# shoe_board-1.net
KiCad netlist of a schematic drawn in EAGLE
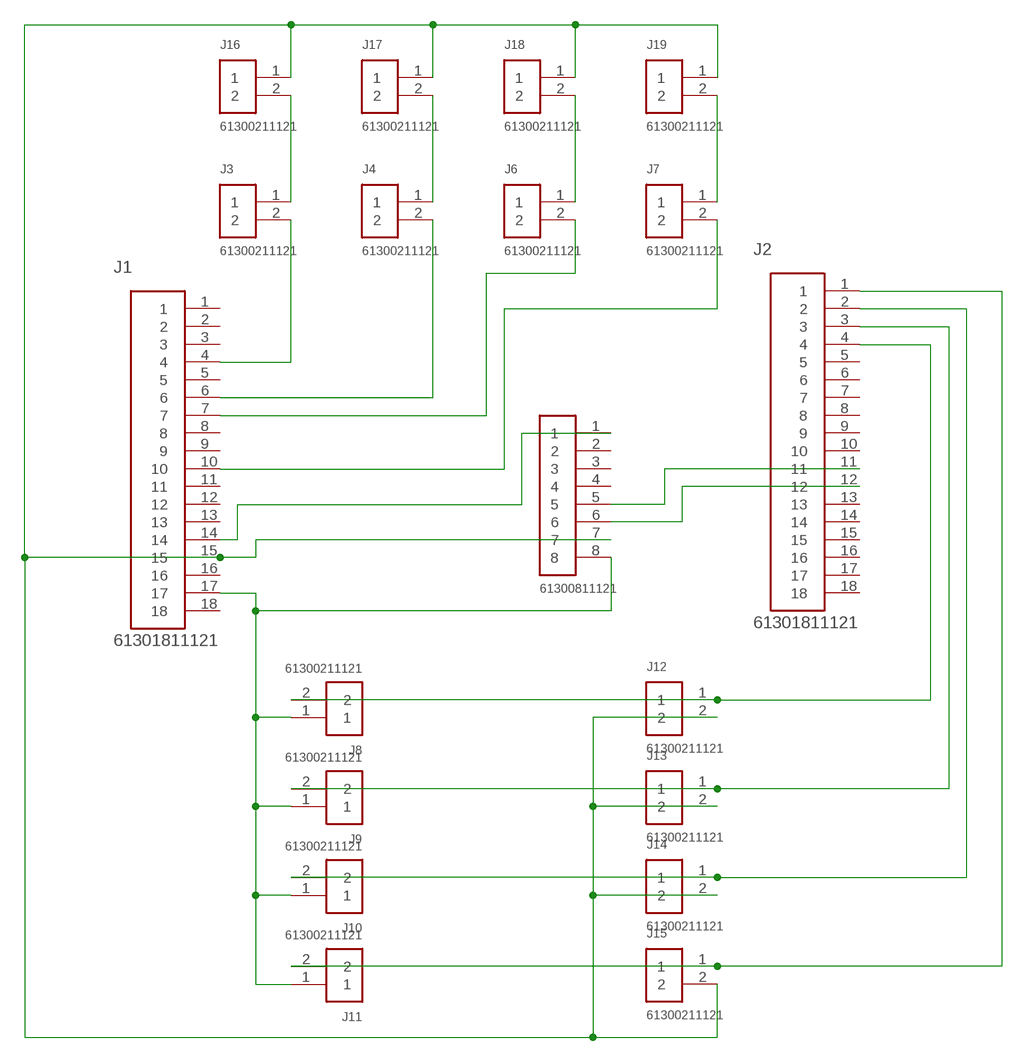
[diagram p0: schematic, sheet 1]

(export (version "E")
  (design (tool "Eeschema 10.0.6"))
  (components
    (comp (ref "J1")
      (value "61301811121")
      (footprint "eagle-import:61301811121")
      (fields
        (field (name "DIGIKEY_PART_NUMBER") "732-5328-ND")
        (field (name "MANUFACTURER") "Wurth Electronics Inc.")
        (field (name "CREATED_BY") "PCBLayout.com")
      )
      (libsource (lib "eagle-import") (part "61301811121"))
    )
    (comp (ref "J2")
      (value "61301811121")
      (footprint "eagle-import:61301811121")
      (fields
        (field (name "DIGIKEY_PART_NUMBER") "732-5328-ND")
        (field (name "MANUFACTURER") "Wurth Electronics Inc.")
        (field (name "CREATED_BY") "PCBLayout.com")
      )
      (libsource (lib "eagle-import") (part "61301811121"))
    )
    (comp (ref "J3")
      (value "61300211121")
      (footprint "eagle-import:61300211121")
      (fields
        (field (name "DIGI_KEY_PART_NUMBER") "732-5315-ND")
        (field (name "MANUFACTURER") "Wurth Electronics Inc.")
        (field (name "CREATED_BY") "PCBLayout.com")
      )
      (libsource (lib "eagle-import") (part "61300211121"))
    )
    (comp (ref "J4")
      (value "61300211121")
      (footprint "eagle-import:61300211121")
      (fields
        (field (name "DIGI_KEY_PART_NUMBER") "732-5315-ND")
        (field (name "MANUFACTURER") "Wurth Electronics Inc.")
        (field (name "CREATED_BY") "PCBLayout.com")
      )
      (libsource (lib "eagle-import") (part "61300211121"))
    )
    (comp (ref "J6")
      (value "61300211121")
      (footprint "eagle-import:61300211121")
      (fields
        (field (name "DIGI_KEY_PART_NUMBER") "732-5315-ND")
        (field (name "MANUFACTURER") "Wurth Electronics Inc.")
        (field (name "CREATED_BY") "PCBLayout.com")
      )
      (libsource (lib "eagle-import") (part "61300211121"))
    )
    (comp (ref "J7")
      (value "61300211121")
      (footprint "eagle-import:61300211121")
      (fields
        (field (name "DIGI_KEY_PART_NUMBER") "732-5315-ND")
        (field (name "MANUFACTURER") "Wurth Electronics Inc.")
        (field (name "CREATED_BY") "PCBLayout.com")
      )
      (libsource (lib "eagle-import") (part "61300211121"))
    )
    (comp (ref "J8")
      (value "61300211121")
      (footprint "eagle-import:61300211121")
      (fields
        (field (name "DIGI_KEY_PART_NUMBER") "732-5315-ND")
        (field (name "MANUFACTURER") "Wurth Electronics Inc.")
        (field (name "CREATED_BY") "PCBLayout.com")
      )
      (libsource (lib "eagle-import") (part "61300211121"))
    )
    (comp (ref "J9")
      (value "61300211121")
      (footprint "eagle-import:61300211121")
      (fields
        (field (name "DIGI_KEY_PART_NUMBER") "732-5315-ND")
        (field (name "MANUFACTURER") "Wurth Electronics Inc.")
        (field (name "CREATED_BY") "PCBLayout.com")
      )
      (libsource (lib "eagle-import") (part "61300211121"))
    )
    (comp (ref "J10")
      (value "61300211121")
      (footprint "eagle-import:61300211121")
      (fields
        (field (name "DIGI_KEY_PART_NUMBER") "732-5315-ND")
        (field (name "MANUFACTURER") "Wurth Electronics Inc.")
        (field (name "CREATED_BY") "PCBLayout.com")
      )
      (libsource (lib "eagle-import") (part "61300211121"))
    )
    (comp (ref "J11")
      (value "61300211121")
      (footprint "eagle-import:61300211121")
      (fields
        (field (name "DIGI_KEY_PART_NUMBER") "732-5315-ND")
        (field (name "MANUFACTURER") "Wurth Electronics Inc.")
        (field (name "CREATED_BY") "PCBLayout.com")
      )
      (libsource (lib "eagle-import") (part "61300211121"))
    )
    (comp (ref "J12")
      (value "61300211121")
      (footprint "eagle-import:61300211121")
      (fields
        (field (name "DIGI_KEY_PART_NUMBER") "732-5315-ND")
        (field (name "MANUFACTURER") "Wurth Electronics Inc.")
        (field (name "CREATED_BY") "PCBLayout.com")
      )
      (libsource (lib "eagle-import") (part "61300211121"))
    )
    (comp (ref "J13")
      (value "61300211121")
      (footprint "eagle-import:61300211121")
      (fields
        (field (name "DIGI_KEY_PART_NUMBER") "732-5315-ND")
        (field (name "MANUFACTURER") "Wurth Electronics Inc.")
        (field (name "CREATED_BY") "PCBLayout.com")
      )
      (libsource (lib "eagle-import") (part "61300211121"))
    )
    (comp (ref "J14")
      (value "61300211121")
      (footprint "eagle-import:61300211121")
      (fields
        (field (name "DIGI_KEY_PART_NUMBER") "732-5315-ND")
        (field (name "MANUFACTURER") "Wurth Electronics Inc.")
        (field (name "CREATED_BY") "PCBLayout.com")
      )
      (libsource (lib "eagle-import") (part "61300211121"))
    )
    (comp (ref "J15")
      (value "61300211121")
      (footprint "eagle-import:61300211121")
      (fields
        (field (name "DIGI_KEY_PART_NUMBER") "732-5315-ND")
        (field (name "MANUFACTURER") "Wurth Electronics Inc.")
        (field (name "CREATED_BY") "PCBLayout.com")
      )
      (libsource (lib "eagle-import") (part "61300211121"))
    )
    (comp (ref "J16")
      (value "61300211121")
      (footprint "eagle-import:61300211121")
      (fields
        (field (name "DIGI_KEY_PART_NUMBER") "732-5315-ND")
        (field (name "MANUFACTURER") "Wurth Electronics Inc.")
        (field (name "CREATED_BY") "PCBLayout.com")
      )
      (libsource (lib "eagle-import") (part "61300211121"))
    )
    (comp (ref "J17")
      (value "61300211121")
      (footprint "eagle-import:61300211121")
      (fields
        (field (name "DIGI_KEY_PART_NUMBER") "732-5315-ND")
        (field (name "MANUFACTURER") "Wurth Electronics Inc.")
        (field (name "CREATED_BY") "PCBLayout.com")
      )
      (libsource (lib "eagle-import") (part "61300211121"))
    )
    (comp (ref "J18")
      (value "61300211121")
      (footprint "eagle-import:61300211121")
      (fields
        (field (name "DIGI_KEY_PART_NUMBER") "732-5315-ND")
        (field (name "MANUFACTURER") "Wurth Electronics Inc.")
        (field (name "CREATED_BY") "PCBLayout.com")
      )
      (libsource (lib "eagle-import") (part "61300211121"))
    )
    (comp (ref "J19")
      (value "61300211121")
      (footprint "eagle-import:61300211121")
      (fields
        (field (name "DIGI_KEY_PART_NUMBER") "732-5315-ND")
        (field (name "MANUFACTURER") "Wurth Electronics Inc.")
        (field (name "CREATED_BY") "PCBLayout.com")
      )
      (libsource (lib "eagle-import") (part "61300211121"))
    )
    (comp (ref "J20")
      (value "61300811121")
      (footprint "eagle-import:61300811121")
      (fields
        (field (name "DIGI_KEY_PART_NUMBER") "732-5321-ND")
        (field (name "MANUFACTURER") "Wurth Electronics Inc.")
        (field (name "CREATED_BY") "PCBLayout.com")
      )
      (libsource (lib "eagle-import") (part "61300811121"))
    )
  )
  (nets
    (net (code "1") (name "Net-(J1-Pad4)") (class "Default")
      (node (ref "J1") (pin "4") (pinfunction "4_4") (pintype "passive"))
      (node (ref "J3") (pin "2") (pinfunction "2_2") (pintype "passive"))
    )
    (net (code "2") (name "Net-(J1-Pad6)") (class "Default")
      (node (ref "J1") (pin "6") (pinfunction "6_6") (pintype "passive"))
      (node (ref "J4") (pin "2") (pinfunction "2_2") (pintype "passive"))
    )
    (net (code "3") (name "Net-(J1-Pad7)") (class "Default")
      (node (ref "J1") (pin "7") (pinfunction "7_7") (pintype "passive"))
      (node (ref "J6") (pin "2") (pinfunction "2_2") (pintype "passive"))
    )
    (net (code "4") (name "Net-(J1-Pad10)") (class "Default")
      (node (ref "J1") (pin "10") (pinfunction "10_10") (pintype "passive"))
      (node (ref "J7") (pin "2") (pinfunction "2_2") (pintype "passive"))
    )
    (net (code "5") (name "Net-(J1-Pad14)") (class "Default")
      (node (ref "J1") (pin "14") (pinfunction "14_14") (pintype "passive"))
      (node (ref "J20") (pin "1") (pinfunction "1_1") (pintype "passive"))
    )
    (net (code "6") (name "Net-(J1-Pad15)") (class "Default")
      (node (ref "J1") (pin "15") (pinfunction "15_15") (pintype "passive"))
      (node (ref "J12") (pin "2") (pinfunction "2_2") (pintype "passive"))
      (node (ref "J13") (pin "2") (pinfunction "2_2") (pintype "passive"))
      (node (ref "J14") (pin "2") (pinfunction "2_2") (pintype "passive"))
      (node (ref "J15") (pin "2") (pinfunction "2_2") (pintype "passive"))
      (node (ref "J16") (pin "1") (pinfunction "1_1") (pintype "passive"))
      (node (ref "J17") (pin "1") (pinfunction "1_1") (pintype "passive"))
      (node (ref "J18") (pin "1") (pinfunction "1_1") (pintype "passive"))
      (node (ref "J19") (pin "1") (pinfunction "1_1") (pintype "passive"))
      (node (ref "J20") (pin "7") (pinfunction "7_7") (pintype "passive"))
    )
    (net (code "7") (name "Net-(J1-Pad17)") (class "Default")
      (node (ref "J1") (pin "17") (pinfunction "17_17") (pintype "passive"))
      (node (ref "J10") (pin "1") (pinfunction "1_1") (pintype "passive"))
      (node (ref "J11") (pin "1") (pinfunction "1_1") (pintype "passive"))
      (node (ref "J20") (pin "8") (pinfunction "8_8") (pintype "passive"))
      (node (ref "J8") (pin "1") (pinfunction "1_1") (pintype "passive"))
      (node (ref "J9") (pin "1") (pinfunction "1_1") (pintype "passive"))
    )
    (net (code "8") (name "Net-(J2-Pad11)") (class "Default")
      (node (ref "J2") (pin "11") (pinfunction "11_11") (pintype "passive"))
      (node (ref "J20") (pin "5") (pinfunction "5_5") (pintype "passive"))
    )
    (net (code "9") (name "Net-(J2-Pad12)") (class "Default")
      (node (ref "J2") (pin "12") (pinfunction "12_12") (pintype "passive"))
      (node (ref "J20") (pin "6") (pinfunction "6_6") (pintype "passive"))
    )
    (net (code "10") (name "Net-(J10-Pad2)") (class "Default")
      (node (ref "J10") (pin "2") (pinfunction "2_2") (pintype "passive"))
      (node (ref "J14") (pin "1") (pinfunction "1_1") (pintype "passive"))
      (node (ref "J2") (pin "2") (pinfunction "2_2") (pintype "passive"))
    )
    (net (code "11") (name "Net-(J11-Pad2)") (class "Default")
      (node (ref "J11") (pin "2") (pinfunction "2_2") (pintype "passive"))
      (node (ref "J15") (pin "1") (pinfunction "1_1") (pintype "passive"))
      (node (ref "J2") (pin "1") (pinfunction "1_1") (pintype "passive"))
    )
    (net (code "12") (name "Net-(J12-Pad1)") (class "Default")
      (node (ref "J12") (pin "1") (pinfunction "1_1") (pintype "passive"))
      (node (ref "J2") (pin "4") (pinfunction "4_4") (pintype "passive"))
      (node (ref "J8") (pin "2") (pinfunction "2_2") (pintype "passive"))
    )
    (net (code "13") (name "Net-(J13-Pad1)") (class "Default")
      (node (ref "J13") (pin "1") (pinfunction "1_1") (pintype "passive"))
      (node (ref "J2") (pin "3") (pinfunction "3_3") (pintype "passive"))
      (node (ref "J9") (pin "2") (pinfunction "2_2") (pintype "passive"))
    )
    (net (code "14") (name "Net-(J16-Pad2)") (class "Default")
      (node (ref "J16") (pin "2") (pinfunction "2_2") (pintype "passive"))
      (node (ref "J3") (pin "1") (pinfunction "1_1") (pintype "passive"))
    )
    (net (code "15") (name "Net-(J17-Pad2)") (class "Default")
      (node (ref "J17") (pin "2") (pinfunction "2_2") (pintype "passive"))
      (node (ref "J4") (pin "1") (pinfunction "1_1") (pintype "passive"))
    )
    (net (code "16") (name "Net-(J18-Pad2)") (class "Default")
      (node (ref "J18") (pin "2") (pinfunction "2_2") (pintype "passive"))
      (node (ref "J6") (pin "1") (pinfunction "1_1") (pintype "passive"))
    )
    (net (code "17") (name "Net-(J19-Pad2)") (class "Default")
      (node (ref "J19") (pin "2") (pinfunction "2_2") (pintype "passive"))
      (node (ref "J7") (pin "1") (pinfunction "1_1") (pintype "passive"))
    )
    (net (code "18") (name "unconnected-(J1-Pad1)") (class "Default")
      (node (ref "J1") (pin "1") (pinfunction "1_1") (pintype "passive"))
    )
    (net (code "19") (name "unconnected-(J1-Pad2)") (class "Default")
      (node (ref "J1") (pin "2") (pinfunction "2_2") (pintype "passive"))
    )
    (net (code "20") (name "unconnected-(J1-Pad3)") (class "Default")
      (node (ref "J1") (pin "3") (pinfunction "3_3") (pintype "passive"))
    )
    (net (code "21") (name "unconnected-(J1-Pad5)") (class "Default")
      (node (ref "J1") (pin "5") (pinfunction "5_5") (pintype "passive"))
    )
    (net (code "22") (name "unconnected-(J1-Pad8)") (class "Default")
      (node (ref "J1") (pin "8") (pinfunction "8_8") (pintype "passive"))
    )
    (net (code "23") (name "unconnected-(J1-Pad9)") (class "Default")
      (node (ref "J1") (pin "9") (pinfunction "9_9") (pintype "passive"))
    )
    (net (code "24") (name "unconnected-(J1-Pad11)") (class "Default")
      (node (ref "J1") (pin "11") (pinfunction "11_11") (pintype "passive"))
    )
    (net (code "25") (name "unconnected-(J1-Pad12)") (class "Default")
      (node (ref "J1") (pin "12") (pinfunction "12_12") (pintype "passive"))
    )
    (net (code "26") (name "unconnected-(J1-Pad13)") (class "Default")
      (node (ref "J1") (pin "13") (pinfunction "13_13") (pintype "passive"))
    )
    (net (code "27") (name "unconnected-(J1-Pad16)") (class "Default")
      (node (ref "J1") (pin "16") (pinfunction "16_16") (pintype "passive"))
    )
    (net (code "28") (name "unconnected-(J1-Pad18)") (class "Default")
      (node (ref "J1") (pin "18") (pinfunction "18_18") (pintype "passive"))
    )
    (net (code "29") (name "unconnected-(J2-Pad5)") (class "Default")
      (node (ref "J2") (pin "5") (pinfunction "5_5") (pintype "passive"))
    )
    (net (code "30") (name "unconnected-(J2-Pad6)") (class "Default")
      (node (ref "J2") (pin "6") (pinfunction "6_6") (pintype "passive"))
    )
    (net (code "31") (name "unconnected-(J2-Pad7)") (class "Default")
      (node (ref "J2") (pin "7") (pinfunction "7_7") (pintype "passive"))
    )
    (net (code "32") (name "unconnected-(J2-Pad8)") (class "Default")
      (node (ref "J2") (pin "8") (pinfunction "8_8") (pintype "passive"))
    )
    (net (code "33") (name "unconnected-(J2-Pad9)") (class "Default")
      (node (ref "J2") (pin "9") (pinfunction "9_9") (pintype "passive"))
    )
    (net (code "34") (name "unconnected-(J2-Pad10)") (class "Default")
      (node (ref "J2") (pin "10") (pinfunction "10_10") (pintype "passive"))
    )
    (net (code "35") (name "unconnected-(J2-Pad13)") (class "Default")
      (node (ref "J2") (pin "13") (pinfunction "13_13") (pintype "passive"))
    )
    (net (code "36") (name "unconnected-(J2-Pad14)") (class "Default")
      (node (ref "J2") (pin "14") (pinfunction "14_14") (pintype "passive"))
    )
    (net (code "37") (name "unconnected-(J2-Pad15)") (class "Default")
      (node (ref "J2") (pin "15") (pinfunction "15_15") (pintype "passive"))
    )
    (net (code "38") (name "unconnected-(J2-Pad16)") (class "Default")
      (node (ref "J2") (pin "16") (pinfunction "16_16") (pintype "passive"))
    )
    (net (code "39") (name "unconnected-(J2-Pad17)") (class "Default")
      (node (ref "J2") (pin "17") (pinfunction "17_17") (pintype "passive"))
    )
    (net (code "40") (name "unconnected-(J2-Pad18)") (class "Default")
      (node (ref "J2") (pin "18") (pinfunction "18_18") (pintype "passive"))
    )
    (net (code "41") (name "unconnected-(J20-Pad2)") (class "Default")
      (node (ref "J20") (pin "2") (pinfunction "2_2") (pintype "passive"))
    )
    (net (code "42") (name "unconnected-(J20-Pad3)") (class "Default")
      (node (ref "J20") (pin "3") (pinfunction "3_3") (pintype "passive"))
    )
    (net (code "43") (name "unconnected-(J20-Pad4)") (class "Default")
      (node (ref "J20") (pin "4") (pinfunction "4_4") (pintype "passive"))
    )
  )
)
